# daughterboard.net
KiCad netlist of a schematic drawn in Altium Designer
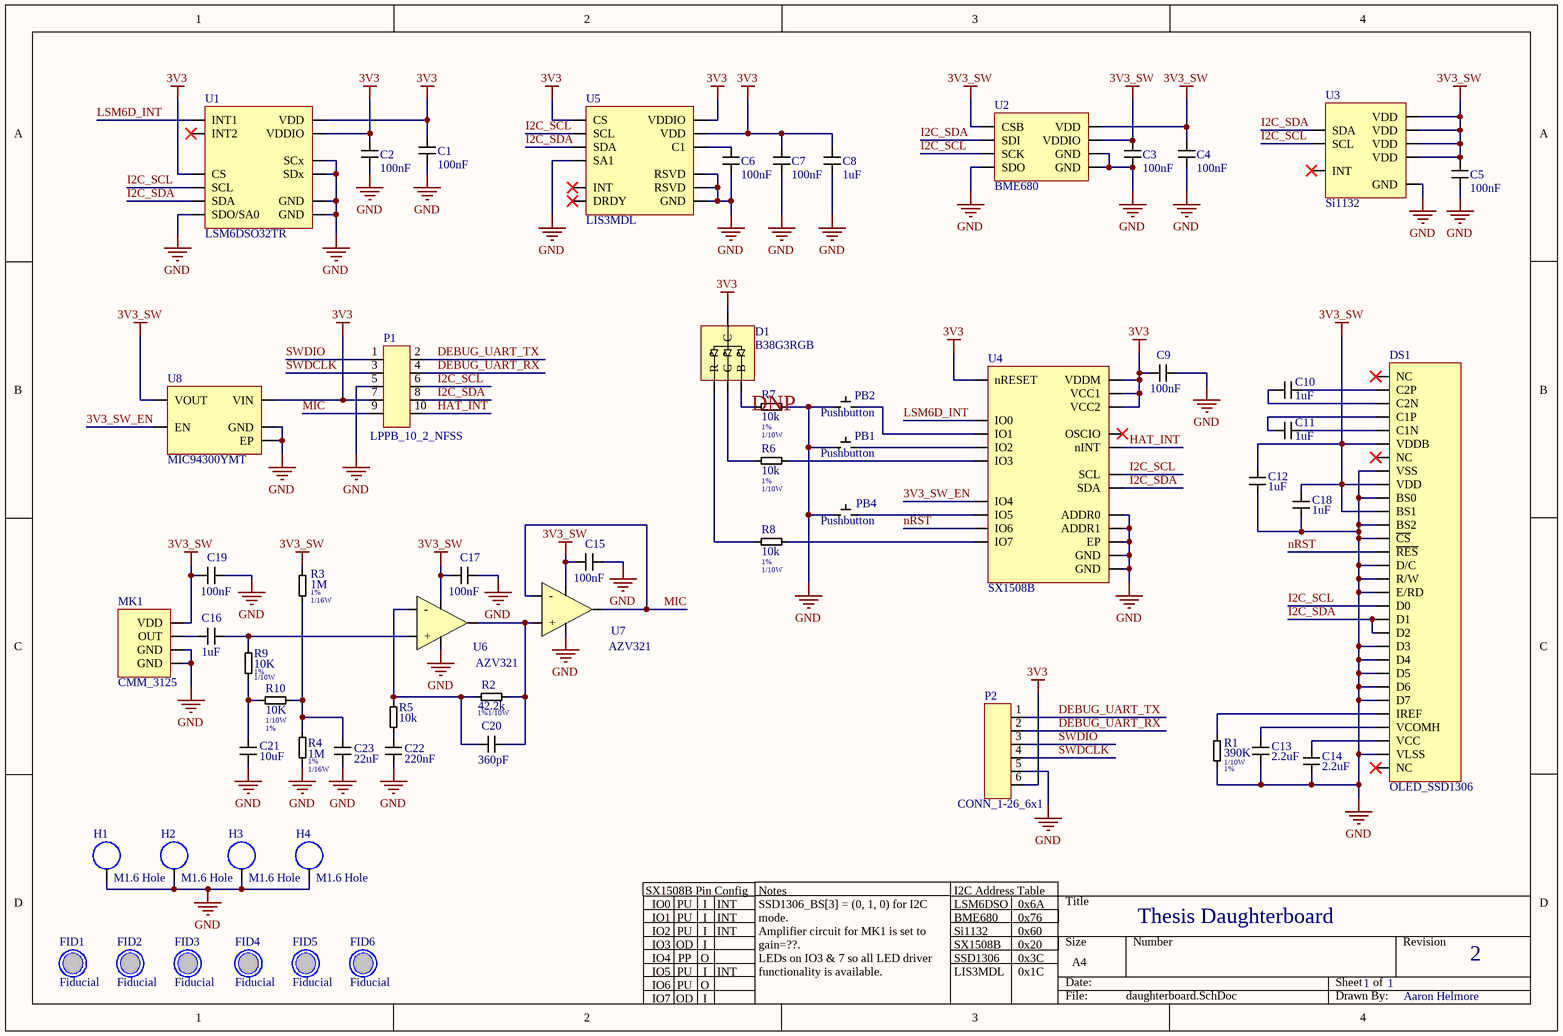
[diagram p0: daughterboard.SchDoc]

(export (version "E")
  (design (tool "Eeschema 10.0.6"))
  (components
    (comp (ref "C1")
      (value "100nF")
      (footprint "CAP_0402")
      (fields (field (name "VOLTAGE") "25V"))
      (libsource (lib "thesis_schem_lib") (part "Capacitor"))
    )
    (comp (ref "C2")
      (value "100nF")
      (footprint "CAP_0402")
      (fields (field (name "VOLTAGE") "25V"))
      (libsource (lib "thesis_schem_lib") (part "Capacitor"))
    )
    (comp (ref "C3")
      (value "100nF")
      (footprint "CAP_0402")
      (fields (field (name "VOLTAGE") "25V"))
      (libsource (lib "thesis_schem_lib") (part "Capacitor"))
    )
    (comp (ref "C4")
      (value "100nF")
      (footprint "CAP_0402")
      (fields (field (name "VOLTAGE") "25V"))
      (libsource (lib "thesis_schem_lib") (part "Capacitor"))
    )
    (comp (ref "C5")
      (value "100nF")
      (footprint "CAP_0402")
      (fields (field (name "VOLTAGE") "25V"))
      (libsource (lib "thesis_schem_lib") (part "Capacitor"))
    )
    (comp (ref "C6")
      (value "100nF")
      (footprint "CAP_0402")
      (fields (field (name "VOLTAGE") "25V"))
      (libsource (lib "thesis_schem_lib") (part "Capacitor"))
    )
    (comp (ref "C7")
      (value "100nF")
      (footprint "CAP_0402")
      (fields (field (name "VOLTAGE") "25V"))
      (libsource (lib "thesis_schem_lib") (part "Capacitor"))
    )
    (comp (ref "C8")
      (value "1uF")
      (footprint "CAP_0402")
      (fields (field (name "VOLTAGE") "25V"))
      (libsource (lib "thesis_schem_lib") (part "Capacitor"))
    )
    (comp (ref "C9")
      (value "100nF")
      (footprint "CAP_0402")
      (fields (field (name "VOLTAGE") "25V"))
      (libsource (lib "thesis_schem_lib") (part "Capacitor"))
    )
    (comp (ref "C10")
      (value "1uF")
      (footprint "CAP_0402")
      (fields (field (name "VOLTAGE") "25V"))
      (libsource (lib "thesis_schem_lib") (part "Capacitor"))
    )
    (comp (ref "C11")
      (value "1uF")
      (footprint "CAP_0402")
      (fields (field (name "VOLTAGE") "25V"))
      (libsource (lib "thesis_schem_lib") (part "Capacitor"))
    )
    (comp (ref "C12")
      (value "1uF")
      (footprint "CAP_0402")
      (fields (field (name "VOLTAGE") "25V"))
      (libsource (lib "thesis_schem_lib") (part "Capacitor"))
    )
    (comp (ref "C13")
      (value "2.2uF")
      (footprint "CAP_0603")
      (fields (field (name "VOLTAGE") "25V"))
      (libsource (lib "thesis_schem_lib") (part "Capacitor"))
    )
    (comp (ref "C14")
      (value "2.2uF")
      (footprint "CAP_0603")
      (fields (field (name "VOLTAGE") "25V"))
      (libsource (lib "thesis_schem_lib") (part "Capacitor"))
    )
    (comp (ref "C15")
      (value "100nF")
      (footprint "CAP_0402")
      (fields (field (name "VOLTAGE") "25V"))
      (libsource (lib "thesis_schem_lib") (part "Capacitor"))
    )
    (comp (ref "C16")
      (value "1uF")
      (footprint "CAP_0402")
      (fields (field (name "VOLTAGE") "25V"))
      (libsource (lib "thesis_schem_lib") (part "Capacitor"))
    )
    (comp (ref "C17")
      (value "100nF")
      (footprint "CAP_0402")
      (fields (field (name "VOLTAGE") "25V"))
      (libsource (lib "thesis_schem_lib") (part "Capacitor"))
    )
    (comp (ref "C18")
      (value "1uF")
      (footprint "CAP_0402")
      (fields (field (name "VOLTAGE") "25V"))
      (libsource (lib "thesis_schem_lib") (part "Capacitor"))
    )
    (comp (ref "C19")
      (value "100nF")
      (footprint "CAP_0402")
      (fields (field (name "VOLTAGE") "25V"))
      (libsource (lib "thesis_schem_lib") (part "Capacitor"))
    )
    (comp (ref "C20")
      (value "360pF")
      (footprint "CAP_0603")
      (fields (field (name "VOLTAGE") "25V"))
      (libsource (lib "thesis_schem_lib") (part "Capacitor"))
    )
    (comp (ref "C21")
      (value "10uF")
      (footprint "CAP_0603")
      (fields (field (name "VOLTAGE") "10V"))
      (libsource (lib "thesis_schem_lib") (part "Capacitor"))
    )
    (comp (ref "C22")
      (value "220nF")
      (footprint "CAP_0603")
      (fields (field (name "VOLTAGE") "25V"))
      (libsource (lib "thesis_schem_lib") (part "Capacitor"))
    )
    (comp (ref "C23")
      (value "22uF")
      (footprint "CAP_0603")
      (fields (field (name "VOLTAGE") "25V"))
      (libsource (lib "thesis_schem_lib") (part "Capacitor"))
    )
    (comp (ref "D1")
      (value "B38G3RGB")
      (footprint "B38G3RGB")
      (description "RGB LED")
      (libsource (lib "thesis_schem_lib") (part "B38G3RGB"))
    )
    (comp (ref "DS1")
      (value "OLED_SSD1306")
      (footprint "OLED_0.96Inch_SSD1306")
      (description "SSD1306 based OLED display")
      (libsource (lib "thesis_schem_lib") (part "OLED_SSD1306"))
    )
    (comp (ref "FID1")
      (value "Fiducial")
      (footprint "FIDUCIAL_0.5MM_SOLDER_1MM_MASK")
      (libsource (lib "thesis_schem_lib") (part "Fiducial"))
    )
    (comp (ref "FID2")
      (value "Fiducial")
      (footprint "FIDUCIAL_0.5MM_SOLDER_1MM_MASK")
      (libsource (lib "thesis_schem_lib") (part "Fiducial"))
    )
    (comp (ref "FID3")
      (value "Fiducial")
      (footprint "FIDUCIAL_0.5MM_SOLDER_1MM_MASK")
      (libsource (lib "thesis_schem_lib") (part "Fiducial"))
    )
    (comp (ref "FID4")
      (value "Fiducial")
      (footprint "FIDUCIAL_0.5MM_SOLDER_1MM_MASK")
      (libsource (lib "thesis_schem_lib") (part "Fiducial"))
    )
    (comp (ref "FID5")
      (value "Fiducial")
      (footprint "FIDUCIAL_0.5MM_SOLDER_1MM_MASK")
      (libsource (lib "thesis_schem_lib") (part "Fiducial"))
    )
    (comp (ref "FID6")
      (value "Fiducial")
      (footprint "FIDUCIAL_0.5MM_SOLDER_1MM_MASK")
      (libsource (lib "thesis_schem_lib") (part "Fiducial"))
    )
    (comp (ref "H1")
      (value "M1.6 Hole")
      (footprint "M1.6")
      (libsource (lib "thesis_schem_lib") (part "M1.6 Mounting Hole"))
    )
    (comp (ref "H2")
      (value "M1.6 Hole")
      (footprint "M1.6")
      (libsource (lib "thesis_schem_lib") (part "M1.6 Mounting Hole"))
    )
    (comp (ref "H3")
      (value "M1.6 Hole")
      (footprint "M1.6")
      (libsource (lib "thesis_schem_lib") (part "M1.6 Mounting Hole"))
    )
    (comp (ref "H4")
      (value "M1.6 Hole")
      (footprint "M1.6")
      (libsource (lib "thesis_schem_lib") (part "M1.6 Mounting Hole"))
    )
    (comp (ref "MK1")
      (value "CMM_3125")
      (footprint "CMM_3125")
      (libsource (lib "thesis_schem_lib") (part "CMM_3125"))
    )
    (comp (ref "P1")
      (value "LPPB_10_2_NFSS")
      (footprint "LPPB_10_2_NFSS")
      (libsource (lib "thesis_schem_lib") (part "LPPB_10_2_NFSS"))
    )
    (comp (ref "P2")
      (value "CONN_1-26_6x1")
      (footprint "851-PP-NNN-40-001101")
      (libsource (lib "thesis_schem_lib") (part "CONN_1-26_6x1"))
    )
    (comp (ref "PB1")
      (value "Pushbutton")
      (footprint "EVQP7A")
      (libsource (lib "thesis_schem_lib") (part "Pushbutton"))
    )
    (comp (ref "PB2")
      (value "Pushbutton")
      (footprint "EVQP7A")
      (libsource (lib "thesis_schem_lib") (part "Pushbutton"))
    )
    (comp (ref "PB4")
      (value "Pushbutton")
      (footprint "EVQP7A")
      (libsource (lib "thesis_schem_lib") (part "Pushbutton"))
    )
    (comp (ref "R1")
      (value "390K")
      (footprint "RES_0402")
      (fields (field (name "WATTAGE") "1/10W") (field (name "TOLERANCE") "1%"))
      (libsource (lib "") (part "R_Small_1"))
    )
    (comp (ref "R2")
      (value "42.2k")
      (footprint "RES_0402")
      (fields (field (name "WATTAGE") "1/10W") (field (name "TOLERANCE") "1%"))
      (libsource (lib "thesis_schem_lib") (part "R_Small"))
    )
    (comp (ref "R3")
      (value "1M")
      (footprint "RES_0402")
      (fields (field (name "WATTAGE") "1/16W") (field (name "TOLERANCE") "1%"))
      (libsource (lib "") (part "R_Small_1"))
    )
    (comp (ref "R4")
      (value "1M")
      (footprint "RES_0402")
      (fields (field (name "WATTAGE") "1/16W") (field (name "TOLERANCE") "1%"))
      (libsource (lib "") (part "R_Small_1"))
    )
    (comp (ref "R5")
      (value "10k")
      (footprint "RES_0402")
      (fields (field (name "TOLERANCE") "1%"))
      (libsource (lib "") (part "R_Small_1"))
    )
    (comp (ref "R6")
      (value "10k")
      (footprint "RES_0402")
      (fields (field (name "TOLERANCE") "1%") (field (name "WATTAGE") "1/10W"))
      (libsource (lib "thesis_schem_lib") (part "R_Small"))
    )
    (comp (ref "R7")
      (value "10k")
      (footprint "RES_0402")
      (fields (field (name "TOLERANCE") "1%") (field (name "WATTAGE") "1/10W"))
      (libsource (lib "thesis_schem_lib") (part "R_Small"))
    )
    (comp (ref "R8")
      (value "10k")
      (footprint "RES_0402")
      (fields (field (name "TOLERANCE") "1%") (field (name "WATTAGE") "1/10W"))
      (libsource (lib "thesis_schem_lib") (part "R_Small"))
    )
    (comp (ref "R9")
      (value "10K")
      (footprint "RES_0402")
      (fields (field (name "WATTAGE") "1/10W") (field (name "TOLERANCE") "1%"))
      (libsource (lib "") (part "R_Small_1"))
    )
    (comp (ref "R10")
      (value "10K")
      (footprint "RES_0402")
      (fields (field (name "WATTAGE") "1/10W") (field (name "TOLERANCE") "1%"))
      (libsource (lib "thesis_schem_lib") (part "R_Small"))
    )
    (comp (ref "U1")
      (value "LSM6DSO32TR")
      (footprint "LSM6DSO")
      (description "STM IMU")
      (libsource (lib "thesis_schem_lib") (part "LSM6DSO32TR"))
    )
    (comp (ref "U2")
      (value "BME680")
      (footprint "BME680")
      (description "Bosch gas, pressure and humidity sensor")
      (libsource (lib "thesis_schem_lib") (part "BME680"))
    )
    (comp (ref "U3")
      (value "Si1132")
      (footprint "Si1132")
      (description "UV index and ambient light sensor")
      (libsource (lib "thesis_schem_lib") (part "Si1132"))
    )
    (comp (ref "U4")
      (value "SX1508B")
      (footprint "QFN40P300X300X60_HS-21N")
      (description "8 channel GPIO expander with level shifting, LED driver and keypad engine")
      (libsource (lib "thesis_schem_lib") (part "SX1508B"))
    )
    (comp (ref "U5")
      (value "LIS3MDL")
      (footprint "LIS3MDL")
      (description "ST magnetometer")
      (libsource (lib "thesis_schem_lib") (part "LIS3MDL"))
    )
    (comp (ref "U6")
      (value "AZV321")
      (footprint "SC-70-5")
      (libsource (lib "thesis_schem_lib") (part "AZV321"))
    )
    (comp (ref "U7")
      (value "AZV321")
      (footprint "SC-70-5")
      (libsource (lib "thesis_schem_lib") (part "AZV321"))
    )
    (comp (ref "U8")
      (value "MIC94300YMT")
      (footprint "MIC94300YMT")
      (description "200mA load switch")
      (libsource (lib "thesis_schem_lib") (part "MIC94300YMT"))
    )
  )
  (nets
    (net (code "1") (name "/3V3_SW_EN") (class "Default")
      (node (ref "U4") (pin "15") (pinfunction "IO4_15") (pintype "passive"))
      (node (ref "U8") (pin "1") (pinfunction "EN_1") (pintype "passive"))
    )
    (net (code "2") (name "/DEBUG_UART_RX") (class "Default")
      (node (ref "P1") (pin "4") (pintype "passive"))
      (node (ref "P2") (pin "2") (pintype "passive"))
    )
    (net (code "3") (name "/DEBUG_UART_TX") (class "Default")
      (node (ref "P1") (pin "2") (pintype "passive"))
      (node (ref "P2") (pin "1") (pintype "passive"))
    )
    (net (code "4") (name "/HAT_INT") (class "Default")
      (node (ref "P1") (pin "10") (pintype "passive"))
      (node (ref "U4") (pin "11") (pinfunction "nINT_11") (pintype "passive"))
    )
    (net (code "5") (name "/I2C_SCL") (class "Default")
      (node (ref "DS1") (pin "18") (pinfunction "D0_18") (pintype "passive"))
      (node (ref "P1") (pin "6") (pintype "passive"))
      (node (ref "U1") (pin "13") (pinfunction "SCL_13") (pintype "passive"))
      (node (ref "U2") (pin "4") (pinfunction "SCK_4") (pintype "passive"))
      (node (ref "U3") (pin "2") (pinfunction "SCL_2") (pintype "passive"))
      (node (ref "U4") (pin "3") (pinfunction "SCL_3") (pintype "passive"))
      (node (ref "U5") (pin "1") (pinfunction "SCL_1") (pintype "passive"))
    )
    (net (code "6") (name "/I2C_SDA") (class "Default")
      (node (ref "DS1") (pin "19") (pinfunction "D1_19") (pintype "passive"))
      (node (ref "DS1") (pin "20") (pinfunction "D2_20") (pintype "passive"))
      (node (ref "P1") (pin "8") (pintype "passive"))
      (node (ref "U1") (pin "14") (pinfunction "SDA_14") (pintype "passive"))
      (node (ref "U2") (pin "3") (pinfunction "SDI_3") (pintype "passive"))
      (node (ref "U3") (pin "1") (pinfunction "SDA_1") (pintype "passive"))
      (node (ref "U4") (pin "2") (pinfunction "SDA_2") (pintype "passive"))
      (node (ref "U5") (pin "11") (pinfunction "SDA_11") (pintype "passive"))
    )
    (net (code "7") (name "/LSM6D_INT") (class "Default")
      (node (ref "U1") (pin "4") (pinfunction "INT1_4") (pintype "passive"))
      (node (ref "U4") (pin "5") (pinfunction "IO0_5") (pintype "passive"))
    )
    (net (code "8") (name "/MIC") (class "Default")
      (node (ref "P1") (pin "9") (pintype "passive"))
      (node (ref "U7") (pin "3") (pinfunction "-_3") (pintype "passive"))
      (node (ref "U7") (pin "4") (pintype "passive"))
    )
    (net (code "9") (name "/SWDCLK") (class "Default")
      (node (ref "P1") (pin "3") (pintype "passive"))
      (node (ref "P2") (pin "4") (pintype "passive"))
    )
    (net (code "10") (name "/SWDIO") (class "Default")
      (node (ref "P1") (pin "1") (pintype "passive"))
      (node (ref "P2") (pin "3") (pintype "passive"))
    )
    (net (code "11") (name "/nRST") (class "Default")
      (node (ref "DS1") (pin "14") (pinfunction "~{RES}_14") (pintype "passive"))
      (node (ref "U4") (pin "19") (pinfunction "IO6_19") (pintype "passive"))
    )
    (net (code "12") (name "3V3") (class "Default")
      (node (ref "C1") (pin "2") (pinfunction "J11_2") (pintype "passive"))
      (node (ref "C2") (pin "2") (pinfunction "J11_2") (pintype "passive"))
      (node (ref "C7") (pin "2") (pinfunction "J11_2") (pintype "passive"))
      (node (ref "C8") (pin "2") (pinfunction "J11_2") (pintype "passive"))
      (node (ref "C9") (pin "2") (pinfunction "J11_2") (pintype "passive"))
      (node (ref "D1") (pin "3") (pinfunction "C_3") (pintype "passive"))
      (node (ref "P1") (pin "7") (pintype "passive"))
      (node (ref "P2") (pin "6") (pintype "passive"))
      (node (ref "U1") (pin "12") (pinfunction "CS_12") (pintype "passive"))
      (node (ref "U1") (pin "5") (pinfunction "VDDIO_5") (pintype "passive"))
      (node (ref "U1") (pin "8") (pinfunction "VDD_8") (pintype "passive"))
      (node (ref "U4") (pin "1") (pinfunction "nRESET_1") (pintype "passive"))
      (node (ref "U4") (pin "14") (pinfunction "VDDM_14") (pintype "passive"))
      (node (ref "U4") (pin "17") (pinfunction "VCC2_17") (pintype "passive"))
      (node (ref "U4") (pin "7") (pinfunction "VCC1_7") (pintype "passive"))
      (node (ref "U5") (pin "10") (pinfunction "CS_10") (pintype "passive"))
      (node (ref "U5") (pin "5") (pinfunction "VDD_5") (pintype "passive"))
      (node (ref "U5") (pin "6") (pinfunction "VDDIO_6") (pintype "passive"))
      (node (ref "U8") (pin "4") (pinfunction "VIN_4") (pintype "passive"))
    )
    (net (code "13") (name "3V3_SW") (class "Default")
      (node (ref "C12") (pin "2") (pinfunction "J11_2") (pintype "passive"))
      (node (ref "C15") (pin "2") (pinfunction "J11_2") (pintype "passive"))
      (node (ref "C17") (pin "2") (pinfunction "J11_2") (pintype "passive"))
      (node (ref "C18") (pin "2") (pinfunction "J11_2") (pintype "passive"))
      (node (ref "C19") (pin "2") (pinfunction "J11_2") (pintype "passive"))
      (node (ref "C3") (pin "2") (pinfunction "J11_2") (pintype "passive"))
      (node (ref "C4") (pin "2") (pinfunction "J11_2") (pintype "passive"))
      (node (ref "C5") (pin "2") (pinfunction "J11_2") (pintype "passive"))
      (node (ref "DS1") (pin "11") (pinfunction "BS1_11") (pintype "passive"))
      (node (ref "DS1") (pin "6") (pinfunction "VDDB_6") (pintype "passive"))
      (node (ref "DS1") (pin "9") (pinfunction "VDD_9") (pintype "passive"))
      (node (ref "MK1") (pin "1") (pinfunction "VDD_1") (pintype "passive"))
      (node (ref "R3") (pin "1") (pinfunction "1_1") (pintype "passive"))
      (node (ref "U2") (pin "2") (pinfunction "CSB_2") (pintype "passive"))
      (node (ref "U2") (pin "6") (pinfunction "VDDIO_6") (pintype "passive"))
      (node (ref "U2") (pin "8") (pinfunction "VDD_8") (pintype "passive"))
      (node (ref "U3") (pin "3") (pinfunction "VDD_3") (pintype "passive"))
      (node (ref "U3") (pin "6") (pinfunction "VDD_6") (pintype "passive"))
      (node (ref "U3") (pin "7") (pinfunction "VDD_7") (pintype "passive"))
      (node (ref "U3") (pin "9") (pinfunction "VDD_9") (pintype "passive"))
      (node (ref "U6") (pin "5") (pintype "passive"))
      (node (ref "U7") (pin "5") (pintype "passive"))
      (node (ref "U8") (pin "3") (pinfunction "VOUT_3") (pintype "passive"))
    )
    (net (code "14") (name "GND") (class "Default")
      (node (ref "C1") (pin "1") (pinfunction "J12_1") (pintype "passive"))
      (node (ref "C12") (pin "1") (pinfunction "J12_1") (pintype "passive"))
      (node (ref "C13") (pin "1") (pinfunction "J12_1") (pintype "passive"))
      (node (ref "C14") (pin "1") (pinfunction "J12_1") (pintype "passive"))
      (node (ref "C15") (pin "1") (pinfunction "J12_1") (pintype "passive"))
      (node (ref "C17") (pin "1") (pinfunction "J12_1") (pintype "passive"))
      (node (ref "C18") (pin "1") (pinfunction "J12_1") (pintype "passive"))
      (node (ref "C19") (pin "1") (pinfunction "J12_1") (pintype "passive"))
      (node (ref "C2") (pin "1") (pinfunction "J12_1") (pintype "passive"))
      (node (ref "C21") (pin "1") (pinfunction "J12_1") (pintype "passive"))
      (node (ref "C22") (pin "1") (pinfunction "J12_1") (pintype "passive"))
      (node (ref "C23") (pin "1") (pinfunction "J12_1") (pintype "passive"))
      (node (ref "C3") (pin "1") (pinfunction "J12_1") (pintype "passive"))
      (node (ref "C4") (pin "1") (pinfunction "J12_1") (pintype "passive"))
      (node (ref "C5") (pin "1") (pinfunction "J12_1") (pintype "passive"))
      (node (ref "C6") (pin "1") (pinfunction "J12_1") (pintype "passive"))
      (node (ref "C7") (pin "1") (pinfunction "J12_1") (pintype "passive"))
      (node (ref "C8") (pin "1") (pinfunction "J12_1") (pintype "passive"))
      (node (ref "C9") (pin "1") (pinfunction "J12_1") (pintype "passive"))
      (node (ref "DS1") (pin "10") (pinfunction "BS0_10") (pintype "passive"))
      (node (ref "DS1") (pin "12") (pinfunction "BS2_12") (pintype "passive"))
      (node (ref "DS1") (pin "13") (pinfunction "~{CS}_13") (pintype "passive"))
      (node (ref "DS1") (pin "15") (pinfunction "D/C_15") (pintype "passive"))
      (node (ref "DS1") (pin "16") (pinfunction "R/W_16") (pintype "passive"))
      (node (ref "DS1") (pin "17") (pinfunction "E/RD_17") (pintype "passive"))
      (node (ref "DS1") (pin "21") (pinfunction "D3_21") (pintype "passive"))
      (node (ref "DS1") (pin "22") (pinfunction "D4_22") (pintype "passive"))
      (node (ref "DS1") (pin "23") (pinfunction "D5_23") (pintype "passive"))
      (node (ref "DS1") (pin "24") (pinfunction "D6_24") (pintype "passive"))
      (node (ref "DS1") (pin "25") (pinfunction "D7_25") (pintype "passive"))
      (node (ref "DS1") (pin "29") (pinfunction "VLSS_29") (pintype "passive"))
      (node (ref "DS1") (pin "8") (pinfunction "VSS_8") (pintype "passive"))
      (node (ref "H1") (pin "1") (pintype "passive"))
      (node (ref "H2") (pin "1") (pintype "passive"))
      (node (ref "H3") (pin "1") (pintype "passive"))
      (node (ref "H4") (pin "1") (pintype "passive"))
      (node (ref "MK1") (pin "2") (pinfunction "GND_2") (pintype "passive"))
      (node (ref "MK1") (pin "3") (pinfunction "GND_3") (pintype "passive"))
      (node (ref "P1") (pin "5") (pintype "passive"))
      (node (ref "P2") (pin "5") (pintype "passive"))
      (node (ref "PB1") (pin "2") (pintype "passive"))
      (node (ref "PB2") (pin "2") (pintype "passive"))
      (node (ref "PB4") (pin "2") (pintype "passive"))
      (node (ref "R1") (pin "2") (pinfunction "2_2") (pintype "passive"))
      (node (ref "R4") (pin "2") (pinfunction "2_2") (pintype "passive"))
      (node (ref "R7") (pin "2") (pinfunction "2_2") (pintype "passive"))
      (node (ref "U1") (pin "1") (pinfunction "SDO/SA0_1") (pintype "passive"))
      (node (ref "U1") (pin "2") (pinfunction "SDx_2") (pintype "passive"))
      (node (ref "U1") (pin "3") (pinfunction "SCx_3") (pintype "passive"))
      (node (ref "U1") (pin "6") (pinfunction "GND_6") (pintype "passive"))
      (node (ref "U1") (pin "7") (pinfunction "GND_7") (pintype "passive"))
      (node (ref "U2") (pin "1") (pinfunction "GND_1") (pintype "passive"))
      (node (ref "U2") (pin "5") (pinfunction "SDO_5") (pintype "passive"))
      (node (ref "U2") (pin "7") (pinfunction "GND_7") (pintype "passive"))
      (node (ref "U3") (pin "8") (pinfunction "GND_8") (pintype "passive"))
      (node (ref "U4") (pin "12") (pinfunction "ADDR1_12") (pintype "passive"))
      (node (ref "U4") (pin "18") (pinfunction "GND_18") (pintype "passive"))
      (node (ref "U4") (pin "21") (pinfunction "EP_21") (pintype "passive"))
      (node (ref "U4") (pin "4") (pinfunction "ADDR0_4") (pintype "passive"))
      (node (ref "U4") (pin "8") (pinfunction "GND_8") (pintype "passive"))
      (node (ref "U5") (pin "12") (pinfunction "RSVD_12") (pintype "passive"))
      (node (ref "U5") (pin "2") (pinfunction "RSVD_2") (pintype "passive"))
      (node (ref "U5") (pin "3") (pinfunction "GND_3") (pintype "passive"))
      (node (ref "U5") (pin "9") (pinfunction "SA1_9") (pintype "passive"))
      (node (ref "U6") (pin "2") (pintype "passive"))
      (node (ref "U7") (pin "2") (pintype "passive"))
      (node (ref "U8") (pin "2") (pinfunction "GND_2") (pintype "passive"))
      (node (ref "U8") (pin "EP1") (pinfunction "EP_EP1") (pintype "passive"))
    )
    (net (code "15") (name "Net-(C6-J11)") (class "Default")
      (node (ref "C6") (pin "2") (pinfunction "J11_2") (pintype "passive"))
      (node (ref "U5") (pin "4") (pinfunction "C1_4") (pintype "passive"))
    )
    (net (code "16") (name "Net-(C10-J11)") (class "Default")
      (node (ref "C10") (pin "2") (pinfunction "J11_2") (pintype "passive"))
      (node (ref "DS1") (pin "3") (pinfunction "C2N_3") (pintype "passive"))
    )
    (net (code "17") (name "Net-(C10-J12)") (class "Default")
      (node (ref "C10") (pin "1") (pinfunction "J12_1") (pintype "passive"))
      (node (ref "DS1") (pin "2") (pinfunction "C2P_2") (pintype "passive"))
    )
    (net (code "18") (name "Net-(C11-J11)") (class "Default")
      (node (ref "C11") (pin "2") (pinfunction "J11_2") (pintype "passive"))
      (node (ref "DS1") (pin "4") (pinfunction "C1P_4") (pintype "passive"))
    )
    (net (code "19") (name "Net-(C11-J12)") (class "Default")
      (node (ref "C11") (pin "1") (pinfunction "J12_1") (pintype "passive"))
      (node (ref "DS1") (pin "5") (pinfunction "C1N_5") (pintype "passive"))
    )
    (net (code "20") (name "Net-(C13-J11)") (class "Default")
      (node (ref "C13") (pin "2") (pinfunction "J11_2") (pintype "passive"))
      (node (ref "DS1") (pin "27") (pinfunction "VCOMH_27") (pintype "passive"))
    )
    (net (code "21") (name "Net-(C14-J11)") (class "Default")
      (node (ref "C14") (pin "2") (pinfunction "J11_2") (pintype "passive"))
      (node (ref "DS1") (pin "28") (pinfunction "VCC_28") (pintype "passive"))
    )
    (net (code "22") (name "Net-(C16-J11)") (class "Default")
      (node (ref "C16") (pin "2") (pinfunction "J11_2") (pintype "passive"))
      (node (ref "MK1") (pin "4") (pinfunction "OUT_4") (pintype "passive"))
    )
    (net (code "23") (name "Net-(C16-J12)") (class "Default")
      (node (ref "C16") (pin "1") (pinfunction "J12_1") (pintype "passive"))
      (node (ref "R9") (pin "1") (pinfunction "1_1") (pintype "passive"))
      (node (ref "U6") (pin "1") (pinfunction "+_1") (pintype "passive"))
    )
    (net (code "24") (name "Net-(C20-J11)") (class "Default")
      (node (ref "C20") (pin "2") (pinfunction "J11_2") (pintype "passive"))
      (node (ref "R2") (pin "1") (pinfunction "1_1") (pintype "passive"))
      (node (ref "R5") (pin "1") (pinfunction "1_1") (pintype "passive"))
      (node (ref "U6") (pin "3") (pinfunction "-_3") (pintype "passive"))
    )
    (net (code "25") (name "Net-(C20-J12)") (class "Default")
      (node (ref "C20") (pin "1") (pinfunction "J12_1") (pintype "passive"))
      (node (ref "R2") (pin "2") (pinfunction "2_2") (pintype "passive"))
      (node (ref "U6") (pin "4") (pintype "passive"))
      (node (ref "U7") (pin "1") (pinfunction "+_1") (pintype "passive"))
    )
    (net (code "26") (name "Net-(C21-J11)") (class "Default")
      (node (ref "C21") (pin "2") (pinfunction "J11_2") (pintype "passive"))
      (node (ref "R10") (pin "1") (pinfunction "1_1") (pintype "passive"))
      (node (ref "R9") (pin "2") (pinfunction "2_2") (pintype "passive"))
    )
    (net (code "27") (name "Net-(C22-J11)") (class "Default")
      (node (ref "C22") (pin "2") (pinfunction "J11_2") (pintype "passive"))
      (node (ref "R5") (pin "2") (pinfunction "2_2") (pintype "passive"))
    )
    (net (code "28") (name "Net-(C23-J11)") (class "Default")
      (node (ref "C23") (pin "2") (pinfunction "J11_2") (pintype "passive"))
      (node (ref "R10") (pin "2") (pinfunction "2_2") (pintype "passive"))
      (node (ref "R3") (pin "2") (pinfunction "2_2") (pintype "passive"))
      (node (ref "R4") (pin "1") (pinfunction "1_1") (pintype "passive"))
    )
    (net (code "29") (name "Net-(D1-B)") (class "Default")
      (node (ref "D1") (pin "2") (pinfunction "B_2") (pintype "passive"))
      (node (ref "R7") (pin "1") (pinfunction "1_1") (pintype "passive"))
    )
    (net (code "30") (name "Net-(D1-G)") (class "Default")
      (node (ref "D1") (pin "1") (pinfunction "G_1") (pintype "passive"))
      (node (ref "R6") (pin "1") (pinfunction "1_1") (pintype "passive"))
    )
    (net (code "31") (name "Net-(D1-R)") (class "Default")
      (node (ref "D1") (pin "4") (pinfunction "R_4") (pintype "passive"))
      (node (ref "R8") (pin "1") (pinfunction "1_1") (pintype "passive"))
    )
    (net (code "32") (name "Net-(DS1-IREF)") (class "Default")
      (node (ref "DS1") (pin "26") (pinfunction "IREF_26") (pintype "passive"))
      (node (ref "R1") (pin "1") (pinfunction "1_1") (pintype "passive"))
    )
    (net (code "33") (name "Net-(U4-IO1)") (class "Default")
      (node (ref "PB2") (pin "1") (pintype "passive"))
      (node (ref "U4") (pin "6") (pinfunction "IO1_6") (pintype "passive"))
    )
    (net (code "34") (name "Net-(U4-IO2)") (class "Default")
      (node (ref "PB1") (pin "1") (pintype "passive"))
      (node (ref "U4") (pin "9") (pinfunction "IO2_9") (pintype "passive"))
    )
    (net (code "35") (name "Net-(U4-IO3)") (class "Default")
      (node (ref "R6") (pin "2") (pinfunction "2_2") (pintype "passive"))
      (node (ref "U4") (pin "10") (pinfunction "IO3_10") (pintype "passive"))
    )
    (net (code "36") (name "Net-(U4-IO5)") (class "Default")
      (node (ref "PB4") (pin "1") (pintype "passive"))
      (node (ref "U4") (pin "16") (pinfunction "IO5_16") (pintype "passive"))
    )
    (net (code "37") (name "Net-(U4-IO7)") (class "Default")
      (node (ref "R8") (pin "2") (pinfunction "2_2") (pintype "passive"))
      (node (ref "U4") (pin "20") (pinfunction "IO7_20") (pintype "passive"))
    )
    (net (code "38") (name "unconnected-(DS1-NC-Pad1)") (class "Default")
      (node (ref "DS1") (pin "1") (pinfunction "NC_1") (pintype "passive+no_connect"))
    )
    (net (code "39") (name "unconnected-(DS1-NC-Pad7)") (class "Default")
      (node (ref "DS1") (pin "7") (pinfunction "NC_7") (pintype "passive+no_connect"))
    )
    (net (code "40") (name "unconnected-(DS1-NC-Pad30)") (class "Default")
      (node (ref "DS1") (pin "30") (pinfunction "NC_30") (pintype "passive+no_connect"))
    )
    (net (code "41") (name "unconnected-(U1-INT2-Pad9)") (class "Default")
      (node (ref "U1") (pin "9") (pinfunction "INT2_9") (pintype "passive+no_connect"))
    )
    (net (code "42") (name "unconnected-(U3-INT-Pad4)") (class "Default")
      (node (ref "U3") (pin "4") (pinfunction "INT_4") (pintype "passive+no_connect"))
    )
    (net (code "43") (name "unconnected-(U4-OSCIO-Pad13)") (class "Default")
      (node (ref "U4") (pin "13") (pinfunction "OSCIO_13") (pintype "passive+no_connect"))
    )
    (net (code "44") (name "unconnected-(U5-DRDY-Pad8)") (class "Default")
      (node (ref "U5") (pin "8") (pinfunction "DRDY_8") (pintype "passive+no_connect"))
    )
    (net (code "45") (name "unconnected-(U5-INT-Pad7)") (class "Default")
      (node (ref "U5") (pin "7") (pinfunction "INT_7") (pintype "passive+no_connect"))
    )
  )
)
